# stspin820.net
KiCad netlist of a schematic drawn in EAGLE
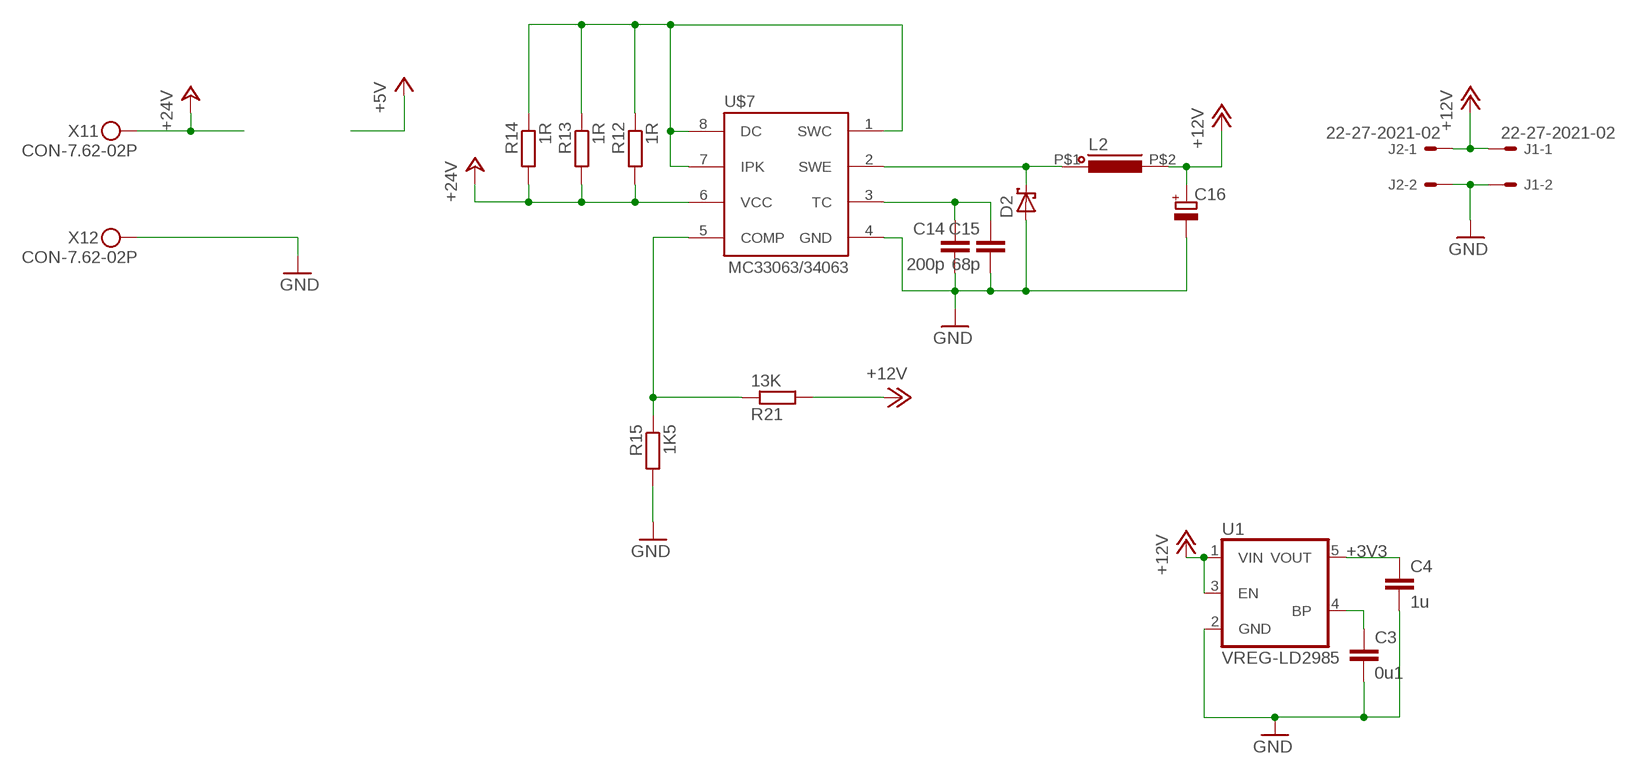
[diagram p0: schematic, sheet 1]
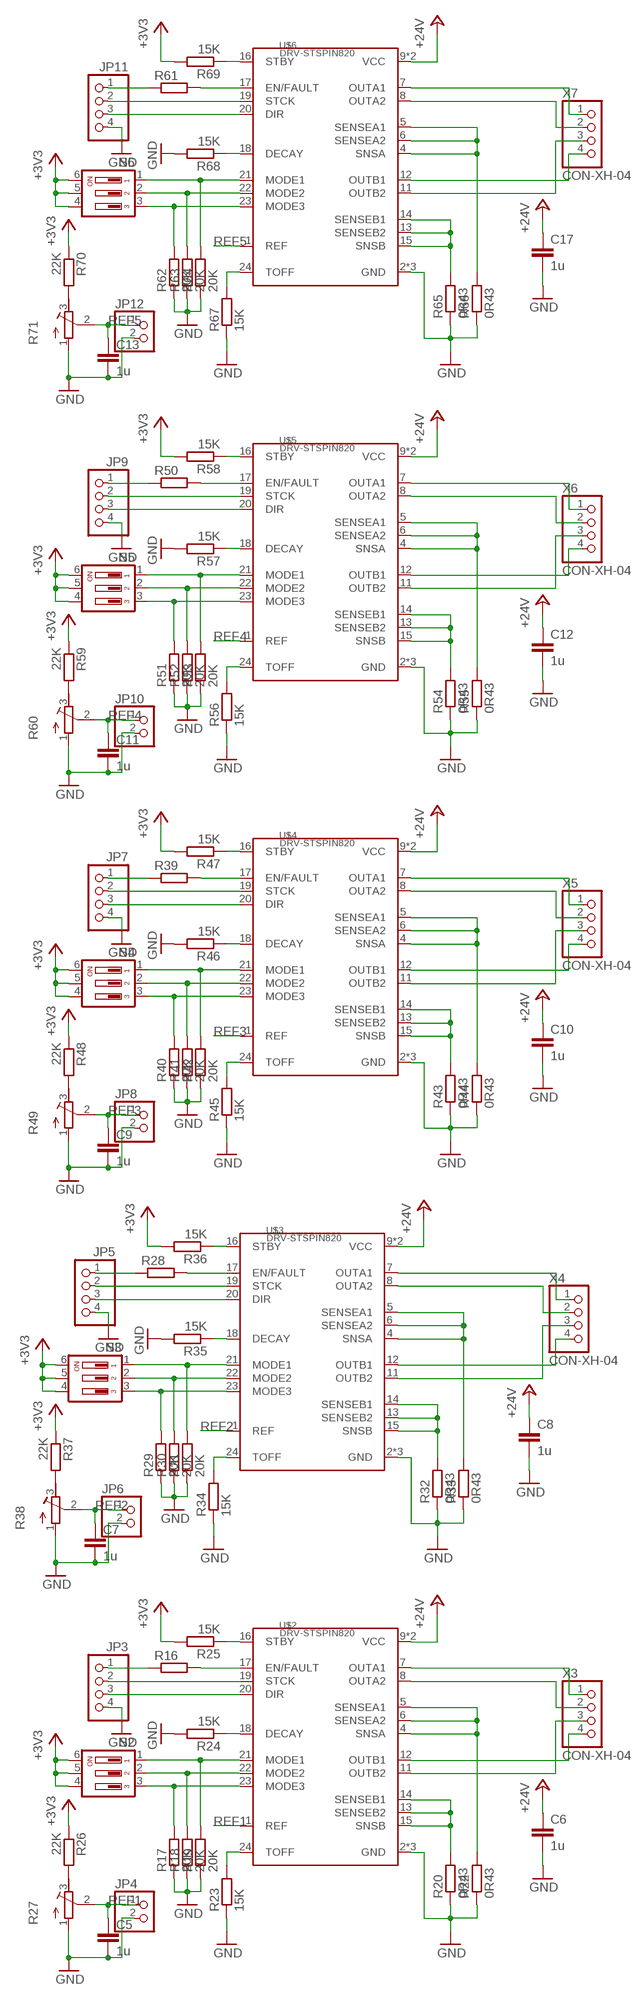
[diagram p1: schematic, sheet 2]

(export (version "E")
  (design (tool "Eeschema 10.0.6"))
  (components
    (comp (ref "C5")
      (value "1u")
      (footprint "eagle-import:CAP0805")
      (libsource (lib "eagle-import") (part "CAP_0805"))
    )
    (comp (ref "C6")
      (value "1u")
      (footprint "eagle-import:CAP0805")
      (libsource (lib "eagle-import") (part "CAP_0805"))
    )
    (comp (ref "C7")
      (value "1u")
      (footprint "eagle-import:CAP0805")
      (libsource (lib "eagle-import") (part "CAP_0805"))
    )
    (comp (ref "C8")
      (value "1u")
      (footprint "eagle-import:CAP0805")
      (libsource (lib "eagle-import") (part "CAP_0805"))
    )
    (comp (ref "C9")
      (value "1u")
      (footprint "eagle-import:CAP0805")
      (libsource (lib "eagle-import") (part "CAP_0805"))
    )
    (comp (ref "C10")
      (value "1u")
      (footprint "eagle-import:CAP0805")
      (libsource (lib "eagle-import") (part "CAP_0805"))
    )
    (comp (ref "C11")
      (value "1u")
      (footprint "eagle-import:CAP0805")
      (libsource (lib "eagle-import") (part "CAP_0805"))
    )
    (comp (ref "C12")
      (value "1u")
      (footprint "eagle-import:CAP0805")
      (libsource (lib "eagle-import") (part "CAP_0805"))
    )
    (comp (ref "C13")
      (value "1u")
      (footprint "eagle-import:CAP0805")
      (libsource (lib "eagle-import") (part "CAP_0805"))
    )
    (comp (ref "C17")
      (value "1u")
      (footprint "eagle-import:CAP0805")
      (libsource (lib "eagle-import") (part "CAP_0805"))
    )
    (comp (ref "JP3")
      (value "PINHD-1X4")
      (footprint "eagle-import:1X04")
      (libsource (lib "eagle-import") (part "PINHD-1X4"))
    )
    (comp (ref "JP4")
      (value "PINHD-1X2")
      (footprint "eagle-import:1X02")
      (libsource (lib "eagle-import") (part "PINHD-1X2"))
    )
    (comp (ref "JP5")
      (value "PINHD-1X4")
      (footprint "eagle-import:1X04")
      (libsource (lib "eagle-import") (part "PINHD-1X4"))
    )
    (comp (ref "JP6")
      (value "PINHD-1X2")
      (footprint "eagle-import:1X02")
      (libsource (lib "eagle-import") (part "PINHD-1X2"))
    )
    (comp (ref "JP7")
      (value "PINHD-1X4")
      (footprint "eagle-import:1X04")
      (libsource (lib "eagle-import") (part "PINHD-1X4"))
    )
    (comp (ref "JP8")
      (value "PINHD-1X2")
      (footprint "eagle-import:1X02")
      (libsource (lib "eagle-import") (part "PINHD-1X2"))
    )
    (comp (ref "JP9")
      (value "PINHD-1X4")
      (footprint "eagle-import:1X04")
      (libsource (lib "eagle-import") (part "PINHD-1X4"))
    )
    (comp (ref "JP10")
      (value "PINHD-1X2")
      (footprint "eagle-import:1X02")
      (libsource (lib "eagle-import") (part "PINHD-1X2"))
    )
    (comp (ref "JP11")
      (value "PINHD-1X4")
      (footprint "eagle-import:1X04")
      (libsource (lib "eagle-import") (part "PINHD-1X4"))
    )
    (comp (ref "JP12")
      (value "PINHD-1X2")
      (footprint "eagle-import:1X02")
      (libsource (lib "eagle-import") (part "PINHD-1X2"))
    )
    (comp (ref "R16")
      (value "R_R0805")
      (footprint "eagle-import:RESC2012X50")
      (libsource (lib "eagle-import") (part "R_R0805"))
    )
    (comp (ref "R17")
      (value "20K")
      (footprint "eagle-import:RESC2012X50")
      (libsource (lib "eagle-import") (part "R_R0805"))
    )
    (comp (ref "R18")
      (value "20K")
      (footprint "eagle-import:RESC2012X50")
      (libsource (lib "eagle-import") (part "R_R0805"))
    )
    (comp (ref "R19")
      (value "20K")
      (footprint "eagle-import:RESC2012X50")
      (libsource (lib "eagle-import") (part "R_R0805"))
    )
    (comp (ref "R20")
      (value "0R43")
      (footprint "eagle-import:RESC3216X60")
      (libsource (lib "eagle-import") (part "R_R1206"))
    )
    (comp (ref "R22")
      (value "0R43")
      (footprint "eagle-import:RESC3216X60")
      (libsource (lib "eagle-import") (part "R_R1206"))
    )
    (comp (ref "R23")
      (value "15K")
      (footprint "eagle-import:RESC2012X50")
      (libsource (lib "eagle-import") (part "R_R0805"))
    )
    (comp (ref "R24")
      (value "15K")
      (footprint "eagle-import:RESC2012X50")
      (libsource (lib "eagle-import") (part "R_R0805"))
    )
    (comp (ref "R25")
      (value "15K")
      (footprint "eagle-import:RESC2012X50")
      (libsource (lib "eagle-import") (part "R_R0805"))
    )
    (comp (ref "R26")
      (value "22K")
      (footprint "eagle-import:RESC2012X50")
      (libsource (lib "eagle-import") (part "R_R0805"))
    )
    (comp (ref "R27")
      (value "R_POT3296X")
      (footprint "eagle-import:POT-3296X")
      (libsource (lib "eagle-import") (part "R_POT3296X"))
    )
    (comp (ref "R28")
      (value "R_R0805")
      (footprint "eagle-import:RESC2012X50")
      (libsource (lib "eagle-import") (part "R_R0805"))
    )
    (comp (ref "R29")
      (value "20K")
      (footprint "eagle-import:RESC2012X50")
      (libsource (lib "eagle-import") (part "R_R0805"))
    )
    (comp (ref "R30")
      (value "20K")
      (footprint "eagle-import:RESC2012X50")
      (libsource (lib "eagle-import") (part "R_R0805"))
    )
    (comp (ref "R31")
      (value "20K")
      (footprint "eagle-import:RESC2012X50")
      (libsource (lib "eagle-import") (part "R_R0805"))
    )
    (comp (ref "R32")
      (value "0R43")
      (footprint "eagle-import:RESC3216X60")
      (libsource (lib "eagle-import") (part "R_R1206"))
    )
    (comp (ref "R33")
      (value "0R43")
      (footprint "eagle-import:RESC3216X60")
      (libsource (lib "eagle-import") (part "R_R1206"))
    )
    (comp (ref "R34")
      (value "15K")
      (footprint "eagle-import:RESC2012X50")
      (libsource (lib "eagle-import") (part "R_R0805"))
    )
    (comp (ref "R35")
      (value "15K")
      (footprint "eagle-import:RESC2012X50")
      (libsource (lib "eagle-import") (part "R_R0805"))
    )
    (comp (ref "R36")
      (value "15K")
      (footprint "eagle-import:RESC2012X50")
      (libsource (lib "eagle-import") (part "R_R0805"))
    )
    (comp (ref "R37")
      (value "22K")
      (footprint "eagle-import:RESC2012X50")
      (libsource (lib "eagle-import") (part "R_R0805"))
    )
    (comp (ref "R38")
      (value "R_POT3296X")
      (footprint "eagle-import:POT-3296X")
      (libsource (lib "eagle-import") (part "R_POT3296X"))
    )
    (comp (ref "R39")
      (value "R_R0805")
      (footprint "eagle-import:RESC2012X50")
      (libsource (lib "eagle-import") (part "R_R0805"))
    )
    (comp (ref "R40")
      (value "20K")
      (footprint "eagle-import:RESC2012X50")
      (libsource (lib "eagle-import") (part "R_R0805"))
    )
    (comp (ref "R41")
      (value "20K")
      (footprint "eagle-import:RESC2012X50")
      (libsource (lib "eagle-import") (part "R_R0805"))
    )
    (comp (ref "R42")
      (value "20K")
      (footprint "eagle-import:RESC2012X50")
      (libsource (lib "eagle-import") (part "R_R0805"))
    )
    (comp (ref "R43")
      (value "0R43")
      (footprint "eagle-import:RESC3216X60")
      (libsource (lib "eagle-import") (part "R_R1206"))
    )
    (comp (ref "R44")
      (value "0R43")
      (footprint "eagle-import:RESC3216X60")
      (libsource (lib "eagle-import") (part "R_R1206"))
    )
    (comp (ref "R45")
      (value "15K")
      (footprint "eagle-import:RESC2012X50")
      (libsource (lib "eagle-import") (part "R_R0805"))
    )
    (comp (ref "R46")
      (value "15K")
      (footprint "eagle-import:RESC2012X50")
      (libsource (lib "eagle-import") (part "R_R0805"))
    )
    (comp (ref "R47")
      (value "15K")
      (footprint "eagle-import:RESC2012X50")
      (libsource (lib "eagle-import") (part "R_R0805"))
    )
    (comp (ref "R48")
      (value "22K")
      (footprint "eagle-import:RESC2012X50")
      (libsource (lib "eagle-import") (part "R_R0805"))
    )
    (comp (ref "R49")
      (value "R_POT3296X")
      (footprint "eagle-import:POT-3296X")
      (libsource (lib "eagle-import") (part "R_POT3296X"))
    )
    (comp (ref "R50")
      (value "R_R0805")
      (footprint "eagle-import:RESC2012X50")
      (libsource (lib "eagle-import") (part "R_R0805"))
    )
    (comp (ref "R51")
      (value "20K")
      (footprint "eagle-import:RESC2012X50")
      (libsource (lib "eagle-import") (part "R_R0805"))
    )
    (comp (ref "R52")
      (value "20K")
      (footprint "eagle-import:RESC2012X50")
      (libsource (lib "eagle-import") (part "R_R0805"))
    )
    (comp (ref "R53")
      (value "20K")
      (footprint "eagle-import:RESC2012X50")
      (libsource (lib "eagle-import") (part "R_R0805"))
    )
    (comp (ref "R54")
      (value "0R43")
      (footprint "eagle-import:RESC3216X60")
      (libsource (lib "eagle-import") (part "R_R1206"))
    )
    (comp (ref "R55")
      (value "0R43")
      (footprint "eagle-import:RESC3216X60")
      (libsource (lib "eagle-import") (part "R_R1206"))
    )
    (comp (ref "R56")
      (value "15K")
      (footprint "eagle-import:RESC2012X50")
      (libsource (lib "eagle-import") (part "R_R0805"))
    )
    (comp (ref "R57")
      (value "15K")
      (footprint "eagle-import:RESC2012X50")
      (libsource (lib "eagle-import") (part "R_R0805"))
    )
    (comp (ref "R58")
      (value "15K")
      (footprint "eagle-import:RESC2012X50")
      (libsource (lib "eagle-import") (part "R_R0805"))
    )
    (comp (ref "R59")
      (value "22K")
      (footprint "eagle-import:RESC2012X50")
      (libsource (lib "eagle-import") (part "R_R0805"))
    )
    (comp (ref "R60")
      (value "R_POT3296X")
      (footprint "eagle-import:POT-3296X")
      (libsource (lib "eagle-import") (part "R_POT3296X"))
    )
    (comp (ref "R61")
      (value "R_R0805")
      (footprint "eagle-import:RESC2012X50")
      (libsource (lib "eagle-import") (part "R_R0805"))
    )
    (comp (ref "R62")
      (value "20K")
      (footprint "eagle-import:RESC2012X50")
      (libsource (lib "eagle-import") (part "R_R0805"))
    )
    (comp (ref "R63")
      (value "20K")
      (footprint "eagle-import:RESC2012X50")
      (libsource (lib "eagle-import") (part "R_R0805"))
    )
    (comp (ref "R64")
      (value "20K")
      (footprint "eagle-import:RESC2012X50")
      (libsource (lib "eagle-import") (part "R_R0805"))
    )
    (comp (ref "R65")
      (value "0R43")
      (footprint "eagle-import:RESC3216X60")
      (libsource (lib "eagle-import") (part "R_R1206"))
    )
    (comp (ref "R66")
      (value "0R43")
      (footprint "eagle-import:RESC3216X60")
      (libsource (lib "eagle-import") (part "R_R1206"))
    )
    (comp (ref "R67")
      (value "15K")
      (footprint "eagle-import:RESC2012X50")
      (libsource (lib "eagle-import") (part "R_R0805"))
    )
    (comp (ref "R68")
      (value "15K")
      (footprint "eagle-import:RESC2012X50")
      (libsource (lib "eagle-import") (part "R_R0805"))
    )
    (comp (ref "R69")
      (value "15K")
      (footprint "eagle-import:RESC2012X50")
      (libsource (lib "eagle-import") (part "R_R0805"))
    )
    (comp (ref "R70")
      (value "22K")
      (footprint "eagle-import:RESC2012X50")
      (libsource (lib "eagle-import") (part "R_R0805"))
    )
    (comp (ref "R71")
      (value "R_POT3296X")
      (footprint "eagle-import:POT-3296X")
      (libsource (lib "eagle-import") (part "R_POT3296X"))
    )
    (comp (ref "S2")
      (value "SW-DIP03S")
      (footprint "eagle-import:DIP03YL")
      (libsource (lib "eagle-import") (part "SW-DIP03S"))
    )
    (comp (ref "S3")
      (value "SW-DIP03S")
      (footprint "eagle-import:DIP03YL")
      (libsource (lib "eagle-import") (part "SW-DIP03S"))
    )
    (comp (ref "S4")
      (value "SW-DIP03S")
      (footprint "eagle-import:DIP03YL")
      (libsource (lib "eagle-import") (part "SW-DIP03S"))
    )
    (comp (ref "S5")
      (value "SW-DIP03S")
      (footprint "eagle-import:DIP03YL")
      (libsource (lib "eagle-import") (part "SW-DIP03S"))
    )
    (comp (ref "S6")
      (value "SW-DIP03S")
      (footprint "eagle-import:DIP03YL")
      (libsource (lib "eagle-import") (part "SW-DIP03S"))
    )
    (comp (ref "U$2")
      (value "DRV-STSPIN820")
      (footprint "eagle-import:QFN24")
      (libsource (lib "eagle-import") (part "DRV-STSPIN820"))
    )
    (comp (ref "U$3")
      (value "DRV-STSPIN820")
      (footprint "eagle-import:QFN24")
      (libsource (lib "eagle-import") (part "DRV-STSPIN820"))
    )
    (comp (ref "U$4")
      (value "DRV-STSPIN820")
      (footprint "eagle-import:QFN24")
      (libsource (lib "eagle-import") (part "DRV-STSPIN820"))
    )
    (comp (ref "U$5")
      (value "DRV-STSPIN820")
      (footprint "eagle-import:QFN24")
      (libsource (lib "eagle-import") (part "DRV-STSPIN820"))
    )
    (comp (ref "U$6")
      (value "DRV-STSPIN820")
      (footprint "eagle-import:QFN24")
      (libsource (lib "eagle-import") (part "DRV-STSPIN820"))
    )
    (comp (ref "X3")
      (value "CON-XH-04")
      (footprint "eagle-import:XH-04")
      (libsource (lib "eagle-import") (part "CON-XH-04"))
    )
    (comp (ref "X4")
      (value "CON-XH-04")
      (footprint "eagle-import:XH-04")
      (libsource (lib "eagle-import") (part "CON-XH-04"))
    )
    (comp (ref "X5")
      (value "CON-XH-04")
      (footprint "eagle-import:XH-04")
      (libsource (lib "eagle-import") (part "CON-XH-04"))
    )
    (comp (ref "X6")
      (value "CON-XH-04")
      (footprint "eagle-import:XH-04")
      (libsource (lib "eagle-import") (part "CON-XH-04"))
    )
    (comp (ref "X7")
      (value "CON-XH-04")
      (footprint "eagle-import:XH-04")
      (libsource (lib "eagle-import") (part "CON-XH-04"))
    )
    (comp (ref "C3")
      (value "0u1")
      (footprint "eagle-import:CAP0805")
      (libsource (lib "eagle-import") (part "CAP_0805"))
    )
    (comp (ref "C4")
      (value "1u")
      (footprint "eagle-import:CAP0805")
      (libsource (lib "eagle-import") (part "CAP_0805"))
    )
    (comp (ref "C14")
      (value "200p")
      (footprint "eagle-import:CAP0805")
      (libsource (lib "eagle-import") (part "CAP_0805"))
    )
    (comp (ref "C15")
      (value "68p")
      (footprint "eagle-import:CAP0805")
      (libsource (lib "eagle-import") (part "CAP_0805"))
    )
    (comp (ref "C16")
      (value "CAP-POL_E3.5-8")
      (footprint "eagle-import:E3,5-8")
      (libsource (lib "eagle-import") (part "CAP-POL_E3.5-8"))
    )
    (comp (ref "D2")
      (value "DIODE-SH_SMA")
      (footprint "eagle-import:DO214AC")
      (libsource (lib "eagle-import") (part "DIODE-SH_SMA"))
    )
    (comp (ref "J1")
      (value "22-27-2021-02")
      (footprint "eagle-import:6410-02")
      (fields (field (name "MF") "MOLEX"))
      (libsource (lib "eagle-import") (part "22-?-0227-2021"))
    )
    (comp (ref "J2")
      (value "22-27-2021-02")
      (footprint "eagle-import:6410-02")
      (fields (field (name "MF") "MOLEX"))
      (libsource (lib "eagle-import") (part "22-?-0227-2021"))
    )
    (comp (ref "L2")
      (value "INDUCTORCW68")
      (footprint "eagle-import:CW68")
      (libsource (lib "eagle-import") (part "INDUCTORCW68"))
    )
    (comp (ref "R12")
      (value "1R")
      (footprint "eagle-import:RESC2012X50")
      (libsource (lib "eagle-import") (part "R_R0805"))
    )
    (comp (ref "R13")
      (value "1R")
      (footprint "eagle-import:RESC2012X50")
      (libsource (lib "eagle-import") (part "R_R0805"))
    )
    (comp (ref "R14")
      (value "1R")
      (footprint "eagle-import:RESC2012X50")
      (libsource (lib "eagle-import") (part "R_R0805"))
    )
    (comp (ref "R15")
      (value "1K5")
      (footprint "eagle-import:RESC2012X50")
      (libsource (lib "eagle-import") (part "R_R0805"))
    )
    (comp (ref "R21")
      (value "13K")
      (footprint "eagle-import:RESC2012X50")
      (libsource (lib "eagle-import") (part "R_R0805"))
    )
    (comp (ref "U$7")
      (value "MC33063/MC34063P")
      (footprint "eagle-import:DIL08")
      (libsource (lib "eagle-import") (part "MC33063/MC34063P"))
    )
    (comp (ref "U1")
      (value "VREG-LD2985")
      (footprint "eagle-import:SOT95P280X145-5")
      (libsource (lib "eagle-import") (part "VREG-LD2985"))
    )
    (comp (ref "X1")
      (value "CON-7.62-02P")
      (footprint "eagle-import:KF25C-7.62-02P-13")
      (libsource (lib "eagle-import") (part "CON-7.62-02P"))
    )
  )
  (nets
    (net (code "1") (name "+3V3") (class "Default")
      (node (ref "C4") (pin "1") (pinfunction "1_1") (pintype "passive"))
      (node (ref "R25") (pin "2") (pinfunction "2_2") (pintype "passive"))
      (node (ref "R26") (pin "1") (pinfunction "1_1") (pintype "passive"))
      (node (ref "R36") (pin "2") (pinfunction "2_2") (pintype "passive"))
      (node (ref "R37") (pin "1") (pinfunction "1_1") (pintype "passive"))
      (node (ref "R47") (pin "2") (pinfunction "2_2") (pintype "passive"))
      (node (ref "R48") (pin "1") (pinfunction "1_1") (pintype "passive"))
      (node (ref "R58") (pin "2") (pinfunction "2_2") (pintype "passive"))
      (node (ref "R59") (pin "1") (pinfunction "1_1") (pintype "passive"))
      (node (ref "R69") (pin "2") (pinfunction "2_2") (pintype "passive"))
      (node (ref "R70") (pin "1") (pinfunction "1_1") (pintype "passive"))
      (node (ref "S2") (pin "4") (pinfunction "4_4") (pintype "passive"))
      (node (ref "S2") (pin "5") (pinfunction "5_5") (pintype "passive"))
      (node (ref "S2") (pin "6") (pinfunction "6_6") (pintype "passive"))
      (node (ref "S3") (pin "4") (pinfunction "4_4") (pintype "passive"))
      (node (ref "S3") (pin "5") (pinfunction "5_5") (pintype "passive"))
      (node (ref "S3") (pin "6") (pinfunction "6_6") (pintype "passive"))
      (node (ref "S4") (pin "4") (pinfunction "4_4") (pintype "passive"))
      (node (ref "S4") (pin "5") (pinfunction "5_5") (pintype "passive"))
      (node (ref "S4") (pin "6") (pinfunction "6_6") (pintype "passive"))
      (node (ref "S5") (pin "4") (pinfunction "4_4") (pintype "passive"))
      (node (ref "S5") (pin "5") (pinfunction "5_5") (pintype "passive"))
      (node (ref "S5") (pin "6") (pinfunction "6_6") (pintype "passive"))
      (node (ref "S6") (pin "4") (pinfunction "4_4") (pintype "passive"))
      (node (ref "S6") (pin "5") (pinfunction "5_5") (pintype "passive"))
      (node (ref "S6") (pin "6") (pinfunction "6_6") (pintype "passive"))
      (node (ref "U1") (pin "5") (pinfunction "VOUT_5") (pintype "passive"))
    )
    (net (code "3") (name "+12V") (class "Default")
      (node (ref "C16") (pin "+") (pinfunction "+_+") (pintype "passive"))
      (node (ref "J1") (pin "1") (pinfunction "S_1") (pintype "passive"))
      (node (ref "J2") (pin "1") (pinfunction "S_1") (pintype "passive"))
      (node (ref "L2") (pin "P$2") (pinfunction "2_P$2") (pintype "passive"))
      (node (ref "R21") (pin "2") (pinfunction "2_2") (pintype "passive"))
      (node (ref "U1") (pin "1") (pinfunction "VIN_1") (pintype "input"))
      (node (ref "U1") (pin "3") (pinfunction "EN_3") (pintype "input"))
    )
    (net (code "4") (name "+24V") (class "Default")
      (node (ref "C10") (pin "1") (pinfunction "1_1") (pintype "passive"))
      (node (ref "C12") (pin "1") (pinfunction "1_1") (pintype "passive"))
      (node (ref "C17") (pin "1") (pinfunction "1_1") (pintype "passive"))
      (node (ref "C6") (pin "1") (pinfunction "1_1") (pintype "passive"))
      (node (ref "C8") (pin "1") (pinfunction "1_1") (pintype "passive"))
      (node (ref "R12") (pin "2") (pinfunction "2_2") (pintype "passive"))
      (node (ref "R13") (pin "2") (pinfunction "2_2") (pintype "passive"))
      (node (ref "R14") (pin "2") (pinfunction "2_2") (pintype "passive"))
      (node (ref "U$2") (pin "10") (pinfunction "VCC_10") (pintype "bidirectional"))
      (node (ref "U$2") (pin "9") (pinfunction "VCC_9") (pintype "bidirectional"))
      (node (ref "U$3") (pin "10") (pinfunction "VCC_10") (pintype "bidirectional"))
      (node (ref "U$3") (pin "9") (pinfunction "VCC_9") (pintype "bidirectional"))
      (node (ref "U$4") (pin "10") (pinfunction "VCC_10") (pintype "bidirectional"))
      (node (ref "U$4") (pin "9") (pinfunction "VCC_9") (pintype "bidirectional"))
      (node (ref "U$5") (pin "10") (pinfunction "VCC_10") (pintype "bidirectional"))
      (node (ref "U$5") (pin "9") (pinfunction "VCC_9") (pintype "bidirectional"))
      (node (ref "U$6") (pin "10") (pinfunction "VCC_10") (pintype "bidirectional"))
      (node (ref "U$6") (pin "9") (pinfunction "VCC_9") (pintype "bidirectional"))
      (node (ref "U$7") (pin "6") (pinfunction "VCC_6") (pintype "power_in"))
      (node (ref "X1") (pin "P$1") (pinfunction "KL_P$1") (pintype "passive"))
    )
    (net (code "5") (name "GND") (class "Default")
      (node (ref "C10") (pin "2") (pinfunction "2_2") (pintype "passive"))
      (node (ref "C11") (pin "2") (pinfunction "2_2") (pintype "passive"))
      (node (ref "C12") (pin "2") (pinfunction "2_2") (pintype "passive"))
      (node (ref "C13") (pin "2") (pinfunction "2_2") (pintype "passive"))
      (node (ref "C14") (pin "2") (pinfunction "2_2") (pintype "passive"))
      (node (ref "C15") (pin "2") (pinfunction "2_2") (pintype "passive"))
      (node (ref "C16") (pin "-") (pinfunction "-_-") (pintype "passive"))
      (node (ref "C17") (pin "2") (pinfunction "2_2") (pintype "passive"))
      (node (ref "C3") (pin "2") (pinfunction "2_2") (pintype "passive"))
      (node (ref "C4") (pin "2") (pinfunction "2_2") (pintype "passive"))
      (node (ref "C5") (pin "2") (pinfunction "2_2") (pintype "passive"))
      (node (ref "C6") (pin "2") (pinfunction "2_2") (pintype "passive"))
      (node (ref "C7") (pin "2") (pinfunction "2_2") (pintype "passive"))
      (node (ref "C8") (pin "2") (pinfunction "2_2") (pintype "passive"))
      (node (ref "C9") (pin "2") (pinfunction "2_2") (pintype "passive"))
      (node (ref "D2") (pin "A") (pinfunction "A_A") (pintype "passive"))
      (node (ref "J1") (pin "2") (pinfunction "S_2") (pintype "passive"))
      (node (ref "J2") (pin "2") (pinfunction "S_2") (pintype "passive"))
      (node (ref "JP10") (pin "2") (pinfunction "2_2") (pintype "passive"))
      (node (ref "JP11") (pin "4") (pinfunction "4_4") (pintype "passive"))
      (node (ref "JP12") (pin "2") (pinfunction "2_2") (pintype "passive"))
      (node (ref "JP3") (pin "4") (pinfunction "4_4") (pintype "passive"))
      (node (ref "JP4") (pin "2") (pinfunction "2_2") (pintype "passive"))
      (node (ref "JP5") (pin "4") (pinfunction "4_4") (pintype "passive"))
      (node (ref "JP6") (pin "2") (pinfunction "2_2") (pintype "passive"))
      (node (ref "JP7") (pin "4") (pinfunction "4_4") (pintype "passive"))
      (node (ref "JP8") (pin "2") (pinfunction "2_2") (pintype "passive"))
      (node (ref "JP9") (pin "4") (pinfunction "4_4") (pintype "passive"))
      (node (ref "R15") (pin "2") (pinfunction "2_2") (pintype "passive"))
      (node (ref "R17") (pin "1") (pinfunction "1_1") (pintype "passive"))
      (node (ref "R18") (pin "1") (pinfunction "1_1") (pintype "passive"))
      (node (ref "R19") (pin "1") (pinfunction "1_1") (pintype "passive"))
      (node (ref "R20") (pin "1") (pinfunction "1_1") (pintype "passive"))
      (node (ref "R22") (pin "1") (pinfunction "1_1") (pintype "passive"))
      (node (ref "R23") (pin "1") (pinfunction "1_1") (pintype "passive"))
      (node (ref "R24") (pin "2") (pinfunction "2_2") (pintype "passive"))
      (node (ref "R27") (pin "1") (pinfunction "A_1") (pintype "passive"))
      (node (ref "R29") (pin "1") (pinfunction "1_1") (pintype "passive"))
      (node (ref "R30") (pin "1") (pinfunction "1_1") (pintype "passive"))
      (node (ref "R31") (pin "1") (pinfunction "1_1") (pintype "passive"))
      (node (ref "R32") (pin "1") (pinfunction "1_1") (pintype "passive"))
      (node (ref "R33") (pin "1") (pinfunction "1_1") (pintype "passive"))
      (node (ref "R34") (pin "1") (pinfunction "1_1") (pintype "passive"))
      (node (ref "R35") (pin "2") (pinfunction "2_2") (pintype "passive"))
      (node (ref "R38") (pin "1") (pinfunction "A_1") (pintype "passive"))
      (node (ref "R40") (pin "1") (pinfunction "1_1") (pintype "passive"))
      (node (ref "R41") (pin "1") (pinfunction "1_1") (pintype "passive"))
      (node (ref "R42") (pin "1") (pinfunction "1_1") (pintype "passive"))
      (node (ref "R43") (pin "1") (pinfunction "1_1") (pintype "passive"))
      (node (ref "R44") (pin "1") (pinfunction "1_1") (pintype "passive"))
      (node (ref "R45") (pin "1") (pinfunction "1_1") (pintype "passive"))
      (node (ref "R46") (pin "2") (pinfunction "2_2") (pintype "passive"))
      (node (ref "R49") (pin "1") (pinfunction "A_1") (pintype "passive"))
      (node (ref "R51") (pin "1") (pinfunction "1_1") (pintype "passive"))
      (node (ref "R52") (pin "1") (pinfunction "1_1") (pintype "passive"))
      (node (ref "R53") (pin "1") (pinfunction "1_1") (pintype "passive"))
      (node (ref "R54") (pin "1") (pinfunction "1_1") (pintype "passive"))
      (node (ref "R55") (pin "1") (pinfunction "1_1") (pintype "passive"))
      (node (ref "R56") (pin "1") (pinfunction "1_1") (pintype "passive"))
      (node (ref "R57") (pin "2") (pinfunction "2_2") (pintype "passive"))
      (node (ref "R60") (pin "1") (pinfunction "A_1") (pintype "passive"))
      (node (ref "R62") (pin "1") (pinfunction "1_1") (pintype "passive"))
      (node (ref "R63") (pin "1") (pinfunction "1_1") (pintype "passive"))
      (node (ref "R64") (pin "1") (pinfunction "1_1") (pintype "passive"))
      (node (ref "R65") (pin "1") (pinfunction "1_1") (pintype "passive"))
      (node (ref "R66") (pin "1") (pinfunction "1_1") (pintype "passive"))
      (node (ref "R67") (pin "1") (pinfunction "1_1") (pintype "passive"))
      (node (ref "R68") (pin "2") (pinfunction "2_2") (pintype "passive"))
      (node (ref "R71") (pin "1") (pinfunction "A_1") (pintype "passive"))
      (node (ref "U$2") (pin "2") (pinfunction "GND_2") (pintype "bidirectional"))
      (node (ref "U$2") (pin "3") (pinfunction "GND_3") (pintype "bidirectional"))
      (node (ref "U$2") (pin "PAD") (pinfunction "GND_PAD") (pintype "bidirectional"))
      (node (ref "U$3") (pin "2") (pinfunction "GND_2") (pintype "bidirectional"))
      (node (ref "U$3") (pin "3") (pinfunction "GND_3") (pintype "bidirectional"))
      (node (ref "U$3") (pin "PAD") (pinfunction "GND_PAD") (pintype "bidirectional"))
      (node (ref "U$4") (pin "2") (pinfunction "GND_2") (pintype "bidirectional"))
      (node (ref "U$4") (pin "3") (pinfunction "GND_3") (pintype "bidirectional"))
      (node (ref "U$4") (pin "PAD") (pinfunction "GND_PAD") (pintype "bidirectional"))
      (node (ref "U$5") (pin "2") (pinfunction "GND_2") (pintype "bidirectional"))
      (node (ref "U$5") (pin "3") (pinfunction "GND_3") (pintype "bidirectional"))
      (node (ref "U$5") (pin "PAD") (pinfunction "GND_PAD") (pintype "bidirectional"))
      (node (ref "U$6") (pin "2") (pinfunction "GND_2") (pintype "bidirectional"))
      (node (ref "U$6") (pin "3") (pinfunction "GND_3") (pintype "bidirectional"))
      (node (ref "U$6") (pin "PAD") (pinfunction "GND_PAD") (pintype "bidirectional"))
      (node (ref "U$7") (pin "4") (pinfunction "GND_4") (pintype "power_in"))
      (node (ref "U1") (pin "2") (pinfunction "GND_2") (pintype "passive"))
      (node (ref "X1") (pin "P$2") (pinfunction "KL_P$2") (pintype "passive"))
    )
    (net (code "6") (name "Net-(JP3-Pad1)") (class "Default")
      (node (ref "JP3") (pin "1") (pinfunction "1_1") (pintype "passive"))
      (node (ref "R16") (pin "1") (pinfunction "1_1") (pintype "passive"))
    )
    (net (code "7") (name "Net-(JP5-Pad1)") (class "Default")
      (node (ref "JP5") (pin "1") (pinfunction "1_1") (pintype "passive"))
      (node (ref "R28") (pin "1") (pinfunction "1_1") (pintype "passive"))
    )
    (net (code "8") (name "Net-(JP7-Pad1)") (class "Default")
      (node (ref "JP7") (pin "1") (pinfunction "1_1") (pintype "passive"))
      (node (ref "R39") (pin "1") (pinfunction "1_1") (pintype "passive"))
    )
    (net (code "9") (name "Net-(JP9-Pad1)") (class "Default")
      (node (ref "JP9") (pin "1") (pinfunction "1_1") (pintype "passive"))
      (node (ref "R50") (pin "1") (pinfunction "1_1") (pintype "passive"))
    )
    (net (code "10") (name "Net-(JP11-Pad1)") (class "Default")
      (node (ref "JP11") (pin "1") (pinfunction "1_1") (pintype "passive"))
      (node (ref "R61") (pin "1") (pinfunction "1_1") (pintype "passive"))
    )
    (net (code "11") (name "Net-(L2-1)") (class "Default")
      (node (ref "D2") (pin "C") (pinfunction "C_C") (pintype "passive"))
      (node (ref "L2") (pin "P$1") (pinfunction "1_P$1") (pintype "passive"))
      (node (ref "U$7") (pin "2") (pinfunction "SWE_2") (pintype "input"))
    )
    (net (code "12") (name "Net-(R27-E)") (class "Default")
      (node (ref "R26") (pin "2") (pinfunction "2_2") (pintype "passive"))
      (node (ref "R27") (pin "3") (pinfunction "E_3") (pintype "passive"))
    )
    (net (code "13") (name "Net-(R38-E)") (class "Default")
      (node (ref "R37") (pin "2") (pinfunction "2_2") (pintype "passive"))
      (node (ref "R38") (pin "3") (pinfunction "E_3") (pintype "passive"))
    )
    (net (code "14") (name "Net-(R49-E)") (class "Default")
      (node (ref "R48") (pin "2") (pinfunction "2_2") (pintype "passive"))
      (node (ref "R49") (pin "3") (pinfunction "E_3") (pintype "passive"))
    )
    (net (code "15") (name "Net-(R60-E)") (class "Default")
      (node (ref "R59") (pin "2") (pinfunction "2_2") (pintype "passive"))
      (node (ref "R60") (pin "3") (pinfunction "E_3") (pintype "passive"))
    )
    (net (code "16") (name "Net-(R71-E)") (class "Default")
      (node (ref "R70") (pin "2") (pinfunction "2_2") (pintype "passive"))
      (node (ref "R71") (pin "3") (pinfunction "E_3") (pintype "passive"))
    )
    (net (code "17") (name "Net-(U$2-DECAY)") (class "Default")
      (node (ref "R24") (pin "1") (pinfunction "1_1") (pintype "passive"))
      (node (ref "U$2") (pin "18") (pinfunction "DECAY_18") (pintype "bidirectional"))
    )
    (net (code "18") (name "Net-(U$2-DIR)") (class "Default")
      (node (ref "JP3") (pin "3") (pinfunction "3_3") (pintype "passive"))
      (node (ref "U$2") (pin "20") (pinfunction "DIR_20") (pintype "bidirectional"))
    )
    (net (code "19") (name "Net-(U$2-EN{slash}FAULT)") (class "Default")
      (node (ref "R16") (pin "2") (pinfunction "2_2") (pintype "passive"))
      (node (ref "U$2") (pin "17") (pinfunction "EN/FAULT_17") (pintype "bidirectional"))
    )
    (net (code "20") (name "Net-(U$2-MODE1)") (class "Default")
      (node (ref "R19") (pin "2") (pinfunction "2_2") (pintype "passive"))
      (node (ref "S2") (pin "1") (pinfunction "1_1") (pintype "passive"))
      (node (ref "U$2") (pin "21") (pinfunction "MODE1_21") (pintype "bidirectional"))
    )
    (net (code "21") (name "Net-(U$2-MODE2)") (class "Default")
      (node (ref "R18") (pin "2") (pinfunction "2_2") (pintype "passive"))
      (node (ref "S2") (pin "2") (pinfunction "2_2") (pintype "passive"))
      (node (ref "U$2") (pin "22") (pinfunction "MODE2_22") (pintype "bidirectional"))
    )
    (net (code "22") (name "Net-(U$2-MODE3)") (class "Default")
      (node (ref "R17") (pin "2") (pinfunction "2_2") (pintype "passive"))
      (node (ref "S2") (pin "3") (pinfunction "3_3") (pintype "passive"))
      (node (ref "U$2") (pin "23") (pinfunction "MODE3_23") (pintype "bidirectional"))
    )
    (net (code "23") (name "Net-(U$2-OUTA1)") (class "Default")
      (node (ref "U$2") (pin "7") (pinfunction "OUTA1_7") (pintype "bidirectional"))
      (node (ref "X3") (pin "1") (pinfunction "1_1") (pintype "passive"))
    )
    (net (code "24") (name "Net-(U$2-OUTA2)") (class "Default")
      (node (ref "U$2") (pin "8") (pinfunction "OUTA2_8") (pintype "bidirectional"))
      (node (ref "X3") (pin "2") (pinfunction "2_2") (pintype "passive"))
    )
    (net (code "25") (name "Net-(U$2-OUTB1)") (class "Default")
      (node (ref "U$2") (pin "12") (pinfunction "OUTB1_12") (pintype "bidirectional"))
      (node (ref "X3") (pin "4") (pinfunction "4_4") (pintype "passive"))
    )
    (net (code "26") (name "Net-(U$2-OUTB2)") (class "Default")
      (node (ref "U$2") (pin "11") (pinfunction "OUTB2_11") (pintype "bidirectional"))
      (node (ref "X3") (pin "3") (pinfunction "3_3") (pintype "passive"))
    )
    (net (code "27") (name "Net-(U$2-SENSEA1)") (class "Default")
      (node (ref "R22") (pin "2") (pinfunction "2_2") (pintype "passive"))
      (node (ref "U$2") (pin "4") (pinfunction "SNSA_4") (pintype "bidirectional"))
      (node (ref "U$2") (pin "5") (pinfunction "SENSEA1_5") (pintype "bidirectional"))
      (node (ref "U$2") (pin "6") (pinfunction "SENSEA2_6") (pintype "bidirectional"))
    )
    (net (code "28") (name "Net-(U$2-SENSEB1)") (class "Default")
      (node (ref "R20") (pin "2") (pinfunction "2_2") (pintype "passive"))
      (node (ref "U$2") (pin "13") (pinfunction "SENSEB2_13") (pintype "bidirectional"))
      (node (ref "U$2") (pin "14") (pinfunction "SENSEB1_14") (pintype "bidirectional"))
      (node (ref "U$2") (pin "15") (pinfunction "SNSB_15") (pintype "bidirectional"))
    )
    (net (code "29") (name "Net-(U$2-STBY)") (class "Default")
      (node (ref "R25") (pin "1") (pinfunction "1_1") (pintype "passive"))
      (node (ref "U$2") (pin "16") (pinfunction "STBY_16") (pintype "bidirectional"))
    )
    (net (code "30") (name "Net-(U$2-STCK)") (class "Default")
      (node (ref "JP3") (pin "2") (pinfunction "2_2") (pintype "passive"))
      (node (ref "U$2") (pin "19") (pinfunction "STCK_19") (pintype "bidirectional"))
    )
    (net (code "31") (name "Net-(U$2-TOFF)") (class "Default")
      (node (ref "R23") (pin "2") (pinfunction "2_2") (pintype "passive"))
      (node (ref "U$2") (pin "24") (pinfunction "TOFF_24") (pintype "bidirectional"))
    )
    (net (code "32") (name "Net-(U$3-DECAY)") (class "Default")
      (node (ref "R35") (pin "1") (pinfunction "1_1") (pintype "passive"))
      (node (ref "U$3") (pin "18") (pinfunction "DECAY_18") (pintype "bidirectional"))
    )
    (net (code "33") (name "Net-(U$3-DIR)") (class "Default")
      (node (ref "JP5") (pin "3") (pinfunction "3_3") (pintype "passive"))
      (node (ref "U$3") (pin "20") (pinfunction "DIR_20") (pintype "bidirectional"))
    )
    (net (code "34") (name "Net-(U$3-EN{slash}FAULT)") (class "Default")
      (node (ref "R28") (pin "2") (pinfunction "2_2") (pintype "passive"))
      (node (ref "U$3") (pin "17") (pinfunction "EN/FAULT_17") (pintype "bidirectional"))
    )
    (net (code "35") (name "Net-(U$3-MODE1)") (class "Default")
      (node (ref "R31") (pin "2") (pinfunction "2_2") (pintype "passive"))
      (node (ref "S3") (pin "1") (pinfunction "1_1") (pintype "passive"))
      (node (ref "U$3") (pin "21") (pinfunction "MODE1_21") (pintype "bidirectional"))
    )
    (net (code "36") (name "Net-(U$3-MODE2)") (class "Default")
      (node (ref "R30") (pin "2") (pinfunction "2_2") (pintype "passive"))
      (node (ref "S3") (pin "2") (pinfunction "2_2") (pintype "passive"))
      (node (ref "U$3") (pin "22") (pinfunction "MODE2_22") (pintype "bidirectional"))
    )
    (net (code "37") (name "Net-(U$3-MODE3)") (class "Default")
      (node (ref "R29") (pin "2") (pinfunction "2_2") (pintype "passive"))
      (node (ref "S3") (pin "3") (pinfunction "3_3") (pintype "passive"))
      (node (ref "U$3") (pin "23") (pinfunction "MODE3_23") (pintype "bidirectional"))
    )
    (net (code "38") (name "Net-(U$3-OUTA1)") (class "Default")
      (node (ref "U$3") (pin "7") (pinfunction "OUTA1_7") (pintype "bidirectional"))
      (node (ref "X4") (pin "1") (pinfunction "1_1") (pintype "passive"))
    )
    (net (code "39") (name "Net-(U$3-OUTA2)") (class "Default")
      (node (ref "U$3") (pin "8") (pinfunction "OUTA2_8") (pintype "bidirectional"))
      (node (ref "X4") (pin "2") (pinfunction "2_2") (pintype "passive"))
    )
    (net (code "40") (name "Net-(U$3-OUTB1)") (class "Default")
      (node (ref "U$3") (pin "12") (pinfunction "OUTB1_12") (pintype "bidirectional"))
      (node (ref "X4") (pin "4") (pinfunction "4_4") (pintype "passive"))
    )
    (net (code "41") (name "Net-(U$3-OUTB2)") (class "Default")
      (node (ref "U$3") (pin "11") (pinfunction "OUTB2_11") (pintype "bidirectional"))
      (node (ref "X4") (pin "3") (pinfunction "3_3") (pintype "passive"))
    )
    (net (code "42") (name "Net-(U$3-SENSEA1)") (class "Default")
      (node (ref "R33") (pin "2") (pinfunction "2_2") (pintype "passive"))
      (node (ref "U$3") (pin "4") (pinfunction "SNSA_4") (pintype "bidirectional"))
      (node (ref "U$3") (pin "5") (pinfunction "SENSEA1_5") (pintype "bidirectional"))
      (node (ref "U$3") (pin "6") (pinfunction "SENSEA2_6") (pintype "bidirectional"))
    )
    (net (code "43") (name "Net-(U$3-SENSEB1)") (class "Default")
      (node (ref "R32") (pin "2") (pinfunction "2_2") (pintype "passive"))
      (node (ref "U$3") (pin "13") (pinfunction "SENSEB2_13") (pintype "bidirectional"))
      (node (ref "U$3") (pin "14") (pinfunction "SENSEB1_14") (pintype "bidirectional"))
      (node (ref "U$3") (pin "15") (pinfunction "SNSB_15") (pintype "bidirectional"))
    )
    (net (code "44") (name "Net-(U$3-STBY)") (class "Default")
      (node (ref "R36") (pin "1") (pinfunction "1_1") (pintype "passive"))
      (node (ref "U$3") (pin "16") (pinfunction "STBY_16") (pintype "bidirectional"))
    )
    (net (code "45") (name "Net-(U$3-STCK)") (class "Default")
      (node (ref "JP5") (pin "2") (pinfunction "2_2") (pintype "passive"))
      (node (ref "U$3") (pin "19") (pinfunction "STCK_19") (pintype "bidirectional"))
    )
    (net (code "46") (name "Net-(U$3-TOFF)") (class "Default")
      (node (ref "R34") (pin "2") (pinfunction "2_2") (pintype "passive"))
      (node (ref "U$3") (pin "24") (pinfunction "TOFF_24") (pintype "bidirectional"))
    )
    (net (code "47") (name "Net-(U$4-DECAY)") (class "Default")
      (node (ref "R46") (pin "1") (pinfunction "1_1") (pintype "passive"))
      (node (ref "U$4") (pin "18") (pinfunction "DECAY_18") (pintype "bidirectional"))
    )
    (net (code "48") (name "Net-(U$4-DIR)") (class "Default")
      (node (ref "JP7") (pin "3") (pinfunction "3_3") (pintype "passive"))
      (node (ref "U$4") (pin "20") (pinfunction "DIR_20") (pintype "bidirectional"))
    )
    (net (code "49") (name "Net-(U$4-EN{slash}FAULT)") (class "Default")
      (node (ref "R39") (pin "2") (pinfunction "2_2") (pintype "passive"))
      (node (ref "U$4") (pin "17") (pinfunction "EN/FAULT_17") (pintype "bidirectional"))
    )
    (net (code "50") (name "Net-(U$4-MODE1)") (class "Default")
      (node (ref "R42") (pin "2") (pinfunction "2_2") (pintype "passive"))
      (node (ref "S4") (pin "1") (pinfunction "1_1") (pintype "passive"))
      (node (ref "U$4") (pin "21") (pinfunction "MODE1_21") (pintype "bidirectional"))
    )
    (net (code "51") (name "Net-(U$4-MODE2)") (class "Default")
      (node (ref "R41") (pin "2") (pinfunction "2_2") (pintype "passive"))
      (node (ref "S4") (pin "2") (pinfunction "2_2") (pintype "passive"))
      (node (ref "U$4") (pin "22") (pinfunction "MODE2_22") (pintype "bidirectional"))
    )
    (net (code "52") (name "Net-(U$4-MODE3)") (class "Default")
      (node (ref "R40") (pin "2") (pinfunction "2_2") (pintype "passive"))
      (node (ref "S4") (pin "3") (pinfunction "3_3") (pintype "passive"))
      (node (ref "U$4") (pin "23") (pinfunction "MODE3_23") (pintype "bidirectional"))
    )
    (net (code "53") (name "Net-(U$4-OUTA1)") (class "Default")
      (node (ref "U$4") (pin "7") (pinfunction "OUTA1_7") (pintype "bidirectional"))
      (node (ref "X5") (pin "1") (pinfunction "1_1") (pintype "passive"))
    )
    (net (code "54") (name "Net-(U$4-OUTA2)") (class "Default")
      (node (ref "U$4") (pin "8") (pinfunction "OUTA2_8") (pintype "bidirectional"))
      (node (ref "X5") (pin "2") (pinfunction "2_2") (pintype "passive"))
    )
    (net (code "55") (name "Net-(U$4-OUTB1)") (class "Default")
      (node (ref "U$4") (pin "12") (pinfunction "OUTB1_12") (pintype "bidirectional"))
      (node (ref "X5") (pin "4") (pinfunction "4_4") (pintype "passive"))
    )
    (net (code "56") (name "Net-(U$4-OUTB2)") (class "Default")
      (node (ref "U$4") (pin "11") (pinfunction "OUTB2_11") (pintype "bidirectional"))
      (node (ref "X5") (pin "3") (pinfunction "3_3") (pintype "passive"))
    )
    (net (code "57") (name "Net-(U$4-SENSEA1)") (class "Default")
      (node (ref "R44") (pin "2") (pinfunction "2_2") (pintype "passive"))
      (node (ref "U$4") (pin "4") (pinfunction "SNSA_4") (pintype "bidirectional"))
      (node (ref "U$4") (pin "5") (pinfunction "SENSEA1_5") (pintype "bidirectional"))
      (node (ref "U$4") (pin "6") (pinfunction "SENSEA2_6") (pintype "bidirectional"))
    )
    (net (code "58") (name "Net-(U$4-SENSEB1)") (class "Default")
      (node (ref "R43") (pin "2") (pinfunction "2_2") (pintype "passive"))
      (node (ref "U$4") (pin "13") (pinfunction "SENSEB2_13") (pintype "bidirectional"))
      (node (ref "U$4") (pin "14") (pinfunction "SENSEB1_14") (pintype "bidirectional"))
      (node (ref "U$4") (pin "15") (pinfunction "SNSB_15") (pintype "bidirectional"))
    )
    (net (code "59") (name "Net-(U$4-STBY)") (class "Default")
      (node (ref "R47") (pin "1") (pinfunction "1_1") (pintype "passive"))
      (node (ref "U$4") (pin "16") (pinfunction "STBY_16") (pintype "bidirectional"))
    )
    (net (code "60") (name "Net-(U$4-STCK)") (class "Default")
      (node (ref "JP7") (pin "2") (pinfunction "2_2") (pintype "passive"))
      (node (ref "U$4") (pin "19") (pinfunction "STCK_19") (pintype "bidirectional"))
    )
    (net (code "61") (name "Net-(U$4-TOFF)") (class "Default")
      (node (ref "R45") (pin "2") (pinfunction "2_2") (pintype "passive"))
      (node (ref "U$4") (pin "24") (pinfunction "TOFF_24") (pintype "bidirectional"))
    )
    (net (code "62") (name "Net-(U$5-DECAY)") (class "Default")
      (node (ref "R57") (pin "1") (pinfunction "1_1") (pintype "passive"))
      (node (ref "U$5") (pin "18") (pinfunction "DECAY_18") (pintype "bidirectional"))
    )
    (net (code "63") (name "Net-(U$5-DIR)") (class "Default")
      (node (ref "JP9") (pin "3") (pinfunction "3_3") (pintype "passive"))
      (node (ref "U$5") (pin "20") (pinfunction "DIR_20") (pintype "bidirectional"))
    )
    (net (code "64") (name "Net-(U$5-EN{slash}FAULT)") (class "Default")
      (node (ref "R50") (pin "2") (pinfunction "2_2") (pintype "passive"))
      (node (ref "U$5") (pin "17") (pinfunction "EN/FAULT_17") (pintype "bidirectional"))
    )
    (net (code "65") (name "Net-(U$5-MODE1)") (class "Default")
      (node (ref "R53") (pin "2") (pinfunction "2_2") (pintype "passive"))
      (node (ref "S5") (pin "1") (pinfunction "1_1") (pintype "passive"))
      (node (ref "U$5") (pin "21") (pinfunction "MODE1_21") (pintype "bidirectional"))
    )
    (net (code "66") (name "Net-(U$5-MODE2)") (class "Default")
      (node (ref "R52") (pin "2") (pinfunction "2_2") (pintype "passive"))
      (node (ref "S5") (pin "2") (pinfunction "2_2") (pintype "passive"))
      (node (ref "U$5") (pin "22") (pinfunction "MODE2_22") (pintype "bidirectional"))
    )
    (net (code "67") (name "Net-(U$5-MODE3)") (class "Default")
      (node (ref "R51") (pin "2") (pinfunction "2_2") (pintype "passive"))
      (node (ref "S5") (pin "3") (pinfunction "3_3") (pintype "passive"))
      (node (ref "U$5") (pin "23") (pinfunction "MODE3_23") (pintype "bidirectional"))
    )
    (net (code "68") (name "Net-(U$5-OUTA1)") (class "Default")
      (node (ref "U$5") (pin "7") (pinfunction "OUTA1_7") (pintype "bidirectional"))
      (node (ref "X6") (pin "1") (pinfunction "1_1") (pintype "passive"))
    )
    (net (code "69") (name "Net-(U$5-OUTA2)") (class "Default")
      (node (ref "U$5") (pin "8") (pinfunction "OUTA2_8") (pintype "bidirectional"))
      (node (ref "X6") (pin "2") (pinfunction "2_2") (pintype "passive"))
    )
    (net (code "70") (name "Net-(U$5-OUTB1)") (class "Default")
      (node (ref "U$5") (pin "12") (pinfunction "OUTB1_12") (pintype "bidirectional"))
      (node (ref "X6") (pin "4") (pinfunction "4_4") (pintype "passive"))
    )
    (net (code "71") (name "Net-(U$5-OUTB2)") (class "Default")
      (node (ref "U$5") (pin "11") (pinfunction "OUTB2_11") (pintype "bidirectional"))
      (node (ref "X6") (pin "3") (pinfunction "3_3") (pintype "passive"))
    )
    (net (code "72") (name "Net-(U$5-SENSEA1)") (class "Default")
      (node (ref "R55") (pin "2") (pinfunction "2_2") (pintype "passive"))
      (node (ref "U$5") (pin "4") (pinfunction "SNSA_4") (pintype "bidirectional"))
      (node (ref "U$5") (pin "5") (pinfunction "SENSEA1_5") (pintype "bidirectional"))
      (node (ref "U$5") (pin "6") (pinfunction "SENSEA2_6") (pintype "bidirectional"))
    )
    (net (code "73") (name "Net-(U$5-SENSEB1)") (class "Default")
      (node (ref "R54") (pin "2") (pinfunction "2_2") (pintype "passive"))
      (node (ref "U$5") (pin "13") (pinfunction "SENSEB2_13") (pintype "bidirectional"))
      (node (ref "U$5") (pin "14") (pinfunction "SENSEB1_14") (pintype "bidirectional"))
      (node (ref "U$5") (pin "15") (pinfunction "SNSB_15") (pintype "bidirectional"))
    )
    (net (code "74") (name "Net-(U$5-STBY)") (class "Default")
      (node (ref "R58") (pin "1") (pinfunction "1_1") (pintype "passive"))
      (node (ref "U$5") (pin "16") (pinfunction "STBY_16") (pintype "bidirectional"))
    )
    (net (code "75") (name "Net-(U$5-STCK)") (class "Default")
      (node (ref "JP9") (pin "2") (pinfunction "2_2") (pintype "passive"))
      (node (ref "U$5") (pin "19") (pinfunction "STCK_19") (pintype "bidirectional"))
    )
    (net (code "76") (name "Net-(U$5-TOFF)") (class "Default")
      (node (ref "R56") (pin "2") (pinfunction "2_2") (pintype "passive"))
      (node (ref "U$5") (pin "24") (pinfunction "TOFF_24") (pintype "bidirectional"))
    )
    (net (code "77") (name "Net-(U$6-DECAY)") (class "Default")
      (node (ref "R68") (pin "1") (pinfunction "1_1") (pintype "passive"))
      (node (ref "U$6") (pin "18") (pinfunction "DECAY_18") (pintype "bidirectional"))
    )
    (net (code "78") (name "Net-(U$6-DIR)") (class "Default")
      (node (ref "JP11") (pin "3") (pinfunction "3_3") (pintype "passive"))
      (node (ref "U$6") (pin "20") (pinfunction "DIR_20") (pintype "bidirectional"))
    )
    (net (code "79") (name "Net-(U$6-EN{slash}FAULT)") (class "Default")
      (node (ref "R61") (pin "2") (pinfunction "2_2") (pintype "passive"))
      (node (ref "U$6") (pin "17") (pinfunction "EN/FAULT_17") (pintype "bidirectional"))
    )
    (net (code "80") (name "Net-(U$6-MODE1)") (class "Default")
      (node (ref "R64") (pin "2") (pinfunction "2_2") (pintype "passive"))
      (node (ref "S6") (pin "1") (pinfunction "1_1") (pintype "passive"))
      (node (ref "U$6") (pin "21") (pinfunction "MODE1_21") (pintype "bidirectional"))
    )
    (net (code "81") (name "Net-(U$6-MODE2)") (class "Default")
      (node (ref "R63") (pin "2") (pinfunction "2_2") (pintype "passive"))
      (node (ref "S6") (pin "2") (pinfunction "2_2") (pintype "passive"))
      (node (ref "U$6") (pin "22") (pinfunction "MODE2_22") (pintype "bidirectional"))
    )
    (net (code "82") (name "Net-(U$6-MODE3)") (class "Default")
      (node (ref "R62") (pin "2") (pinfunction "2_2") (pintype "passive"))
      (node (ref "S6") (pin "3") (pinfunction "3_3") (pintype "passive"))
      (node (ref "U$6") (pin "23") (pinfunction "MODE3_23") (pintype "bidirectional"))
    )
    (net (code "83") (name "Net-(U$6-OUTA1)") (class "Default")
      (node (ref "U$6") (pin "7") (pinfunction "OUTA1_7") (pintype "bidirectional"))
      (node (ref "X7") (pin "1") (pinfunction "1_1") (pintype "passive"))
    )
    (net (code "84") (name "Net-(U$6-OUTA2)") (class "Default")
      (node (ref "U$6") (pin "8") (pinfunction "OUTA2_8") (pintype "bidirectional"))
      (node (ref "X7") (pin "2") (pinfunction "2_2") (pintype "passive"))
    )
    (net (code "85") (name "Net-(U$6-OUTB1)") (class "Default")
      (node (ref "U$6") (pin "12") (pinfunction "OUTB1_12") (pintype "bidirectional"))
      (node (ref "X7") (pin "4") (pinfunction "4_4") (pintype "passive"))
    )
    (net (code "86") (name "Net-(U$6-OUTB2)") (class "Default")
      (node (ref "U$6") (pin "11") (pinfunction "OUTB2_11") (pintype "bidirectional"))
      (node (ref "X7") (pin "3") (pinfunction "3_3") (pintype "passive"))
    )
    (net (code "87") (name "Net-(U$6-SENSEA1)") (class "Default")
      (node (ref "R66") (pin "2") (pinfunction "2_2") (pintype "passive"))
      (node (ref "U$6") (pin "4") (pinfunction "SNSA_4") (pintype "bidirectional"))
      (node (ref "U$6") (pin "5") (pinfunction "SENSEA1_5") (pintype "bidirectional"))
      (node (ref "U$6") (pin "6") (pinfunction "SENSEA2_6") (pintype "bidirectional"))
    )
    (net (code "88") (name "Net-(U$6-SENSEB1)") (class "Default")
      (node (ref "R65") (pin "2") (pinfunction "2_2") (pintype "passive"))
      (node (ref "U$6") (pin "13") (pinfunction "SENSEB2_13") (pintype "bidirectional"))
      (node (ref "U$6") (pin "14") (pinfunction "SENSEB1_14") (pintype "bidirectional"))
      (node (ref "U$6") (pin "15") (pinfunction "SNSB_15") (pintype "bidirectional"))
    )
    (net (code "89") (name "Net-(U$6-STBY)") (class "Default")
      (node (ref "R69") (pin "1") (pinfunction "1_1") (pintype "passive"))
      (node (ref "U$6") (pin "16") (pinfunction "STBY_16") (pintype "bidirectional"))
    )
    (net (code "90") (name "Net-(U$6-STCK)") (class "Default")
      (node (ref "JP11") (pin "2") (pinfunction "2_2") (pintype "passive"))
      (node (ref "U$6") (pin "19") (pinfunction "STCK_19") (pintype "bidirectional"))
    )
    (net (code "91") (name "Net-(U$6-TOFF)") (class "Default")
      (node (ref "R67") (pin "2") (pinfunction "2_2") (pintype "passive"))
      (node (ref "U$6") (pin "24") (pinfunction "TOFF_24") (pintype "bidirectional"))
    )
    (net (code "92") (name "Net-(U$7-COMP)") (class "Default")
      (node (ref "R15") (pin "1") (pinfunction "1_1") (pintype "passive"))
      (node (ref "R21") (pin "1") (pinfunction "1_1") (pintype "passive"))
      (node (ref "U$7") (pin "5") (pinfunction "COMP_5") (pintype "input"))
    )
    (net (code "93") (name "Net-(U$7-DC)") (class "Default")
      (node (ref "R12") (pin "1") (pinfunction "1_1") (pintype "passive"))
      (node (ref "R13") (pin "1") (pinfunction "1_1") (pintype "passive"))
      (node (ref "R14") (pin "1") (pinfunction "1_1") (pintype "passive"))
      (node (ref "U$7") (pin "1") (pinfunction "SWC_1") (pintype "input"))
      (node (ref "U$7") (pin "7") (pinfunction "IPK_7") (pintype "bidirectional"))
      (node (ref "U$7") (pin "8") (pinfunction "DC_8") (pintype "input"))
    )
    (net (code "94") (name "Net-(U$7-TC)") (class "Default")
      (node (ref "C14") (pin "1") (pinfunction "1_1") (pintype "passive"))
      (node (ref "C15") (pin "1") (pinfunction "1_1") (pintype "passive"))
      (node (ref "U$7") (pin "3") (pinfunction "TC_3") (pintype "input"))
    )
    (net (code "95") (name "Net-(U1-BP)") (class "Default")
      (node (ref "C3") (pin "1") (pinfunction "1_1") (pintype "passive"))
      (node (ref "U1") (pin "4") (pinfunction "BP_4") (pintype "input"))
    )
    (net (code "96") (name "REF1") (class "Default")
      (node (ref "C5") (pin "1") (pinfunction "1_1") (pintype "passive"))
      (node (ref "JP4") (pin "1") (pinfunction "1_1") (pintype "passive"))
      (node (ref "R27") (pin "2") (pinfunction "S_2") (pintype "passive"))
      (node (ref "U$2") (pin "1") (pinfunction "REF_1") (pintype "bidirectional"))
    )
    (net (code "97") (name "REF2") (class "Default")
      (node (ref "C7") (pin "1") (pinfunction "1_1") (pintype "passive"))
      (node (ref "JP6") (pin "1") (pinfunction "1_1") (pintype "passive"))
      (node (ref "R38") (pin "2") (pinfunction "S_2") (pintype "passive"))
      (node (ref "U$3") (pin "1") (pinfunction "REF_1") (pintype "bidirectional"))
    )
    (net (code "98") (name "REF3") (class "Default")
      (node (ref "C9") (pin "1") (pinfunction "1_1") (pintype "passive"))
      (node (ref "JP8") (pin "1") (pinfunction "1_1") (pintype "passive"))
      (node (ref "R49") (pin "2") (pinfunction "S_2") (pintype "passive"))
      (node (ref "U$4") (pin "1") (pinfunction "REF_1") (pintype "bidirectional"))
    )
    (net (code "99") (name "REF4") (class "Default")
      (node (ref "C11") (pin "1") (pinfunction "1_1") (pintype "passive"))
      (node (ref "JP10") (pin "1") (pinfunction "1_1") (pintype "passive"))
      (node (ref "R60") (pin "2") (pinfunction "S_2") (pintype "passive"))
      (node (ref "U$5") (pin "1") (pinfunction "REF_1") (pintype "bidirectional"))
    )
    (net (code "100") (name "REF5") (class "Default")
      (node (ref "C13") (pin "1") (pinfunction "1_1") (pintype "passive"))
      (node (ref "JP12") (pin "1") (pinfunction "1_1") (pintype "passive"))
      (node (ref "R71") (pin "2") (pinfunction "S_2") (pintype "passive"))
      (node (ref "U$6") (pin "1") (pinfunction "REF_1") (pintype "bidirectional"))
    )
  )
)
